# Sheet1.net
KiCad netlist of a schematic drawn in Altium Designer
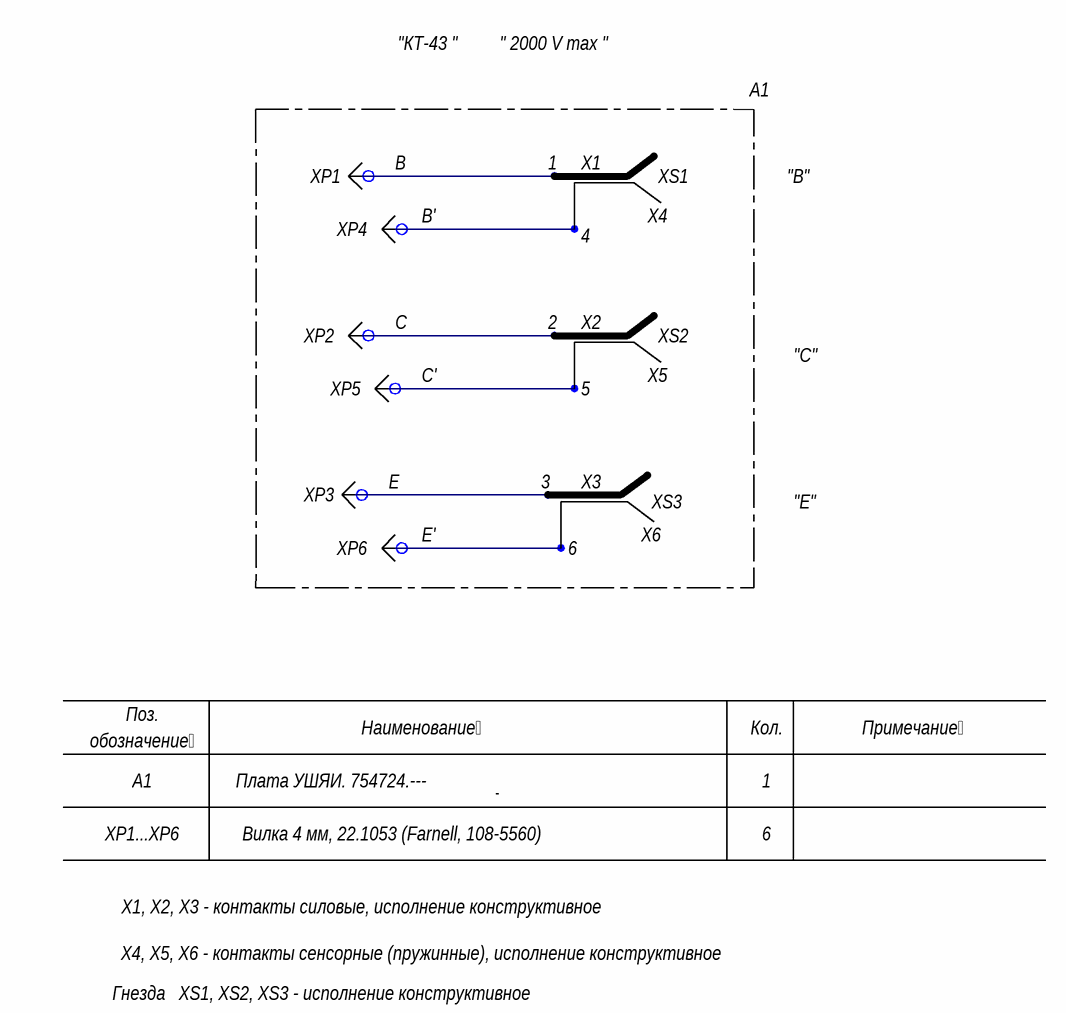
[diagram p0: Sheet1.SCHDOC]

(export (version "E")
  (design (tool "Eeschema 10.0.6"))
  (components
    (comp (ref "U1") (value "XP (LEFT)") (libsource (lib "*") (part "XP (LEFT)")))
    (comp (ref "U5") (value "XP (LEFT)") (libsource (lib "*") (part "XP (LEFT)")))
    (comp (ref "U7") (value "XP (LEFT)") (libsource (lib "*") (part "XP (LEFT)")))
    (comp (ref "U9") (value "XP (LEFT)") (libsource (lib "*") (part "XP (LEFT)")))
    (comp (ref "U15") (value "XP (LEFT)") (libsource (lib "*") (part "XP (LEFT)")))
    (comp (ref "U16") (value "XP (LEFT)") (libsource (lib "*") (part "XP (LEFT)")))
    (comp (ref "U207") (value "POINT (VERY SMALL)") (libsource (lib "*") (part "POINT (VERY SMALL)")))
    (comp (ref "U208") (value "POINT (VERY SMALL)") (libsource (lib "*") (part "POINT (VERY SMALL)")))
    (comp (ref "U209") (value "POINT (VERY SMALL)") (libsource (lib "*") (part "POINT (VERY SMALL)")))
    (comp (ref "U214") (value "POINT (VERY SMALL)") (libsource (lib "*") (part "POINT (VERY SMALL)")))
    (comp (ref "U215") (value "POINT (VERY SMALL)") (libsource (lib "*") (part "POINT (VERY SMALL)")))
    (comp (ref "U216") (value "POINT (VERY SMALL)") (libsource (lib "*") (part "POINT (VERY SMALL)")))
  )
  (nets
    (net (code "1") (name "Net-(U1-Pad0)") (class "Default")
      (node (ref "U1") (pin "0") (pinfunction "0_0") (pintype "passive"))
      (node (ref "U208") (pin "0") (pinfunction "0_0") (pintype "passive"))
    )
    (net (code "2") (name "Net-(U15-Pad0)") (class "Default")
      (node (ref "U15") (pin "0") (pinfunction "0_0") (pintype "passive"))
      (node (ref "U216") (pin "0") (pinfunction "0_0") (pintype "passive"))
    )
    (net (code "3") (name "Net-(U16-Pad0)") (class "Default")
      (node (ref "U16") (pin "0") (pinfunction "0_0") (pintype "passive"))
      (node (ref "U214") (pin "0") (pinfunction "0_0") (pintype "passive"))
    )
    (net (code "4") (name "Net-(U207-Pad0)") (class "Default")
      (node (ref "U207") (pin "0") (pinfunction "0_0") (pintype "passive"))
      (node (ref "U7") (pin "0") (pinfunction "0_0") (pintype "passive"))
    )
    (net (code "5") (name "Net-(U209-Pad0)") (class "Default")
      (node (ref "U209") (pin "0") (pinfunction "0_0") (pintype "passive"))
      (node (ref "U5") (pin "0") (pinfunction "0_0") (pintype "passive"))
    )
    (net (code "6") (name "Net-(U215-Pad0)") (class "Default")
      (node (ref "U215") (pin "0") (pinfunction "0_0") (pintype "passive"))
      (node (ref "U9") (pin "0") (pinfunction "0_0") (pintype "passive"))
    )
  )
)
